# PAGE3.net
KiCad netlist of a schematic drawn in Altium Designer
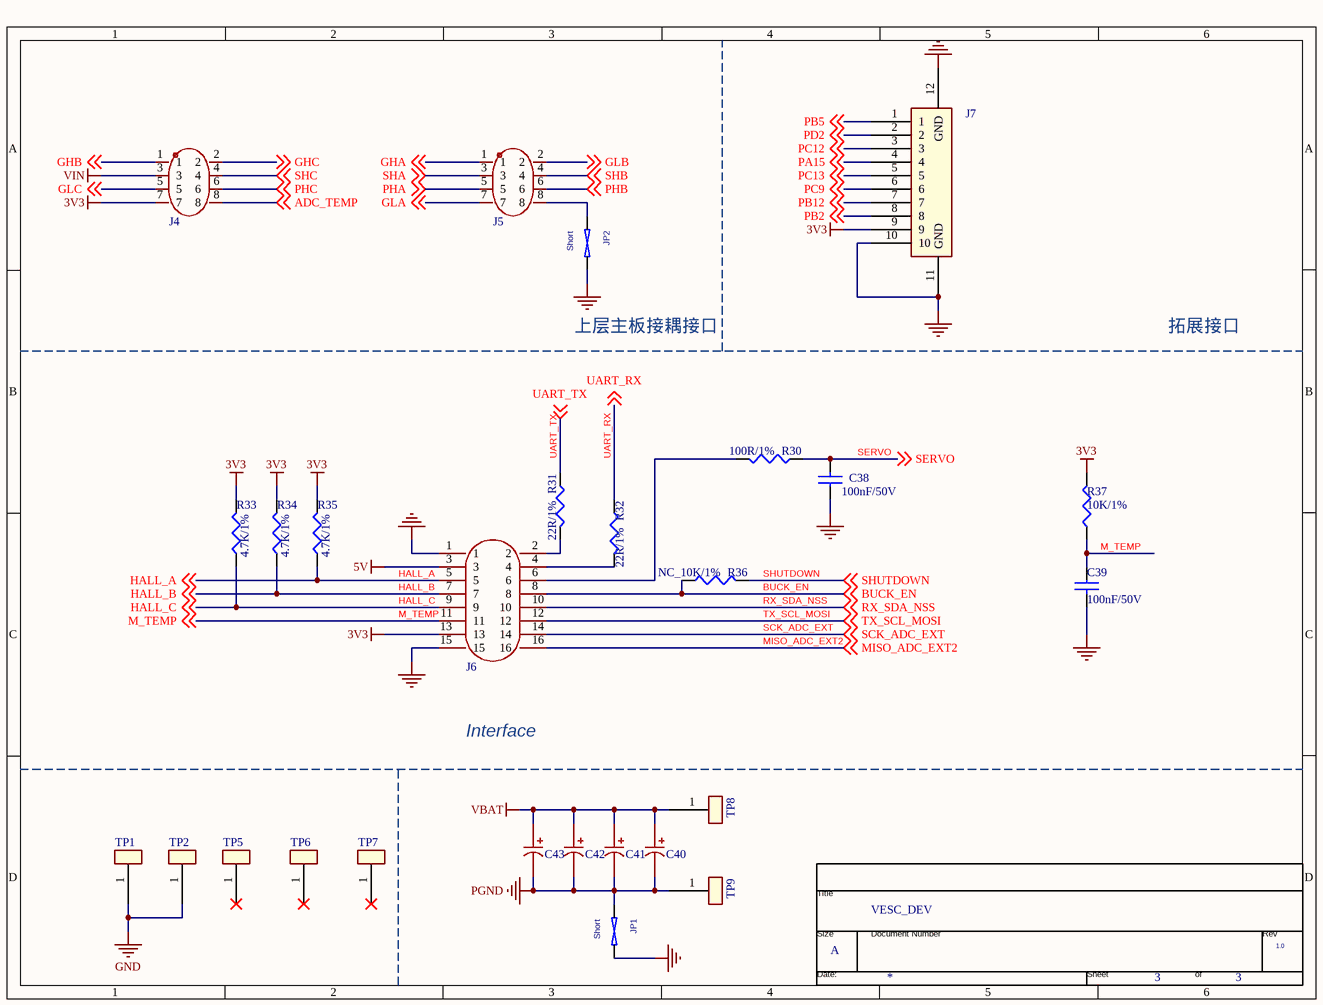
[diagram p0: PAGE3.SchDoc]

(export (version "E")
  (design (tool "Eeschema 10.0.6"))
  (components
    (comp (ref "C38") (value "100nF/50V") (footprint "C0402") (libsource (lib "*") (part "CAP NP")))
    (comp (ref "C39") (value "100nF/50V") (footprint "C0402") (libsource (lib "*") (part "CAP NP")))
    (comp (ref "C40")
      (value "680uF")
      (footprint "CAP-TH_BD10.0-P5.00-D0.6-FD")
      (description "容值:680uF;精度:±20%;额定电压:35V;纹波电流:-;等效串联电阻:-;")
      (fields (field (name "MANUFACTURER") "AISHI(艾华集团)") (field (name "MANUFACTURER PART") "ERS1VM681G16OT"))
      (libsource (lib "VESC_DEVICE_Library") (part "ERS1VM681G16OT"))
    )
    (comp (ref "C41")
      (value "680uF")
      (footprint "CAP-TH_BD10.0-P5.00-D0.6-FD")
      (description "容值:680uF;精度:±20%;额定电压:35V;纹波电流:-;等效串联电阻:-;")
      (fields (field (name "MANUFACTURER") "AISHI(艾华集团)") (field (name "MANUFACTURER PART") "ERS1VM681G16OT"))
      (libsource (lib "VESC_DEVICE_Library") (part "ERS1VM681G16OT"))
    )
    (comp (ref "C42")
      (value "680uF")
      (footprint "CAP-TH_BD10.0-P5.00-D0.6-FD")
      (description "容值:680uF;精度:±20%;额定电压:35V;纹波电流:-;等效串联电阻:-;")
      (fields (field (name "MANUFACTURER") "AISHI(艾华集团)") (field (name "MANUFACTURER PART") "ERS1VM681G16OT"))
      (libsource (lib "VESC_DEVICE_Library") (part "ERS1VM681G16OT"))
    )
    (comp (ref "C43")
      (value "680uF")
      (footprint "CAP-TH_BD10.0-P5.00-D0.6-FD")
      (description "容值:680uF;精度:±20%;额定电压:35V;纹波电流:-;等效串联电阻:-;")
      (fields (field (name "MANUFACTURER") "AISHI(艾华集团)") (field (name "MANUFACTURER PART") "ERS1VM681G16OT"))
      (libsource (lib "VESC_DEVICE_Library") (part "ERS1VM681G16OT"))
    )
    (comp (ref "J4")
      (value "X6521WVS-2x04H-C60D74")
      (footprint "HDR-SMD_8P-P1.27-V-M-C2-C4-LS5.3")
      (fields (field (name "MANUFACTURER") "XKB Connection(中国星坤)"))
      (libsource (lib "VESC_DEVICE_Library") (part "X6521WVS-2x04H-C60D74"))
    )
    (comp (ref "J5")
      (value "X6521WVS-2x04H-C60D74")
      (footprint "HDR-SMD_8P-P1.27-V-M-C2-C4-LS5.3")
      (fields (field (name "MANUFACTURER") "XKB Connection(中国星坤)"))
      (libsource (lib "VESC_DEVICE_Library") (part "X6521WVS-2x04H-C60D74"))
    )
    (comp (ref "J6")
      (value "HC-5557-2*8A")
      (footprint "CONN-TH_HC5557-2X8A")
      (fields (field (name "MANUFACTURER") "HCTL(华灿天禄)"))
      (libsource (lib "VESC_DEVICE_Library") (part "HC-5557-2*8A"))
    )
    (comp (ref "J7")
      (value "1.25-10GH_1")
      (footprint "CONN-SMD_10P-P1.25_JS_GH125-S10CCA-00")
      (libsource (lib "VESC_DEVICE_Library") (part "1.25-10GH_1"))
    )
    (comp (ref "JP1")
      (value "Short")
      (footprint "SHORT")
      (description "2 PIN SHORTED TO CONNECT DIFFERENT NETS")
      (fields (field (name "PART_NUMBER") "TMP-442"))
      (libsource (lib "VESC_DEVICE_Library") (part "SHORT"))
    )
    (comp (ref "JP2")
      (value "Short")
      (footprint "SHORT")
      (description "2 PIN SHORTED TO CONNECT DIFFERENT NETS")
      (fields (field (name "PART_NUMBER") "TMP-442"))
      (libsource (lib "VESC_DEVICE_Library") (part "SHORT"))
    )
    (comp (ref "R30") (value "100R/1%") (footprint "R0402") (libsource (lib "*") (part "RESISTOR")))
    (comp (ref "R31") (value "22R/1%") (footprint "R0402") (libsource (lib "*") (part "RESISTOR")))
    (comp (ref "R32") (value "22R/1%") (footprint "R0402") (libsource (lib "*") (part "RESISTOR")))
    (comp (ref "R33") (value "4.7K/1%") (footprint "R0402") (libsource (lib "*") (part "RESISTOR")))
    (comp (ref "R34") (value "4.7K/1%") (footprint "R0402") (libsource (lib "*") (part "RESISTOR")))
    (comp (ref "R35") (value "4.7K/1%") (footprint "R0402") (libsource (lib "*") (part "RESISTOR")))
    (comp (ref "R36") (value "NC_10K/1%") (footprint "R0402") (libsource (lib "*") (part "RESISTOR")))
    (comp (ref "R37") (value "10K/1%") (footprint "R0402") (libsource (lib "*") (part "RESISTOR")))
    (comp (ref "TP1")
      (value "TEST POINT")
      (footprint "HOLE-4MM_M")
      (libsource (lib "") (part "TEST POINT_1"))
    )
    (comp (ref "TP2")
      (value "TEST POINT")
      (footprint "HOLE-4MM_M")
      (libsource (lib "") (part "TEST POINT_1"))
    )
    (comp (ref "TP5")
      (value "TEST POINT")
      (footprint "HOLE-8MM_M")
      (libsource (lib "") (part "TEST POINT_1"))
    )
    (comp (ref "TP6")
      (value "TEST POINT")
      (footprint "HOLE-8MM_M")
      (libsource (lib "") (part "TEST POINT_1"))
    )
    (comp (ref "TP7")
      (value "TEST POINT")
      (footprint "HOLE-8MM_M")
      (libsource (lib "") (part "TEST POINT_1"))
    )
    (comp (ref "TP8")
      (value "TEST POINT")
      (footprint "HOLE-8MM_M")
      (libsource (lib "VESC_DEVICE_Library") (part "TEST POINT"))
    )
    (comp (ref "TP9")
      (value "TEST POINT")
      (footprint "HOLE-8MM_M")
      (libsource (lib "VESC_DEVICE_Library") (part "TEST POINT"))
    )
  )
  (nets
    (net (code "1") (name "3V3") (class "Default")
      (node (ref "J4") (pin "7") (pinfunction "7_7") (pintype "passive"))
      (node (ref "J6") (pin "13") (pinfunction "13_13") (pintype "passive"))
      (node (ref "J7") (pin "9") (pinfunction "9_9") (pintype "passive"))
      (node (ref "R33") (pin "2") (pinfunction "2_2") (pintype "passive"))
      (node (ref "R34") (pin "2") (pinfunction "2_2") (pintype "passive"))
      (node (ref "R35") (pin "2") (pinfunction "2_2") (pintype "passive"))
      (node (ref "R37") (pin "2") (pinfunction "2_2") (pintype "passive"))
    )
    (net (code "2") (name "5V") (class "Default")
      (node (ref "J6") (pin "3") (pinfunction "3_3") (pintype "passive"))
    )
    (net (code "3") (name "ADC_TEMP") (class "Default")
      (node (ref "J4") (pin "8") (pinfunction "8_8") (pintype "passive"))
    )
    (net (code "4") (name "BUCK_EN") (class "Default")
      (node (ref "J6") (pin "8") (pinfunction "8_8") (pintype "passive"))
      (node (ref "R36") (pin "2") (pinfunction "2_2") (pintype "passive"))
    )
    (net (code "5") (name "GHA") (class "Default")
      (node (ref "J5") (pin "1") (pinfunction "1_1") (pintype "passive"))
    )
    (net (code "6") (name "GHB") (class "Default")
      (node (ref "J4") (pin "1") (pinfunction "1_1") (pintype "passive"))
    )
    (net (code "7") (name "GHC") (class "Default")
      (node (ref "J4") (pin "2") (pinfunction "2_2") (pintype "passive"))
    )
    (net (code "8") (name "GLA") (class "Default")
      (node (ref "J5") (pin "7") (pinfunction "7_7") (pintype "passive"))
    )
    (net (code "9") (name "GLB") (class "Default")
      (node (ref "J5") (pin "2") (pinfunction "2_2") (pintype "passive"))
    )
    (net (code "10") (name "GLC") (class "Default")
      (node (ref "J4") (pin "5") (pinfunction "5_5") (pintype "passive"))
    )
    (net (code "11") (name "GND") (class "Default")
      (node (ref "C38") (pin "1") (pinfunction "1_1") (pintype "passive"))
      (node (ref "C39") (pin "2") (pinfunction "2_2") (pintype "passive"))
      (node (ref "J6") (pin "1") (pinfunction "1_1") (pintype "passive"))
      (node (ref "J6") (pin "15") (pinfunction "15_15") (pintype "passive"))
      (node (ref "J7") (pin "10") (pinfunction "10_10") (pintype "passive"))
      (node (ref "J7") (pin "11") (pinfunction "GND_11") (pintype "passive"))
      (node (ref "J7") (pin "12") (pinfunction "GND_12") (pintype "passive"))
      (node (ref "JP1") (pin "2") (pinfunction "2_2") (pintype "passive"))
      (node (ref "JP2") (pin "2") (pinfunction "2_2") (pintype "passive"))
      (node (ref "TP1") (pin "1") (pinfunction "1_1") (pintype "passive"))
      (node (ref "TP2") (pin "1") (pinfunction "1_1") (pintype "passive"))
    )
    (net (code "12") (name "HALL_A") (class "Default")
      (node (ref "J6") (pin "5") (pinfunction "5_5") (pintype "passive"))
      (node (ref "R35") (pin "1") (pinfunction "1_1") (pintype "passive"))
    )
    (net (code "13") (name "HALL_B") (class "Default")
      (node (ref "J6") (pin "7") (pinfunction "7_7") (pintype "passive"))
      (node (ref "R34") (pin "1") (pinfunction "1_1") (pintype "passive"))
    )
    (net (code "14") (name "HALL_C") (class "Default")
      (node (ref "J6") (pin "9") (pinfunction "9_9") (pintype "passive"))
      (node (ref "R33") (pin "1") (pinfunction "1_1") (pintype "passive"))
    )
    (net (code "15") (name "MISO_ADC_EXT2") (class "Default")
      (node (ref "J6") (pin "16") (pinfunction "16_16") (pintype "passive"))
    )
    (net (code "16") (name "M_TEMP") (class "Default")
      (node (ref "C39") (pin "1") (pinfunction "1_1") (pintype "passive"))
      (node (ref "J6") (pin "11") (pinfunction "11_11") (pintype "passive"))
      (node (ref "R37") (pin "1") (pinfunction "1_1") (pintype "passive"))
    )
    (net (code "17") (name "Net-(J5-Pad8)") (class "Default")
      (node (ref "J5") (pin "8") (pinfunction "8_8") (pintype "passive"))
      (node (ref "JP2") (pin "1") (pinfunction "1_1") (pintype "passive"))
    )
    (net (code "18") (name "Net-(J6-Pad2)") (class "Default")
      (node (ref "J6") (pin "2") (pinfunction "2_2") (pintype "passive"))
      (node (ref "R31") (pin "1") (pinfunction "1_1") (pintype "passive"))
    )
    (net (code "19") (name "Net-(J6-Pad4)") (class "Default")
      (node (ref "J6") (pin "4") (pinfunction "4_4") (pintype "passive"))
      (node (ref "R32") (pin "1") (pinfunction "1_1") (pintype "passive"))
    )
    (net (code "20") (name "Net-(J6-Pad6)") (class "Default")
      (node (ref "J6") (pin "6") (pinfunction "6_6") (pintype "passive"))
      (node (ref "R30") (pin "1") (pinfunction "1_1") (pintype "passive"))
    )
    (net (code "21") (name "PA15") (class "Default")
      (node (ref "J7") (pin "4") (pinfunction "4_4") (pintype "passive"))
    )
    (net (code "22") (name "PB2") (class "Default")
      (node (ref "J7") (pin "8") (pinfunction "8_8") (pintype "passive"))
    )
    (net (code "23") (name "PB5") (class "Default")
      (node (ref "J7") (pin "1") (pinfunction "1_1") (pintype "passive"))
    )
    (net (code "24") (name "PB12") (class "Default")
      (node (ref "J7") (pin "7") (pinfunction "7_7") (pintype "passive"))
    )
    (net (code "25") (name "PC9") (class "Default")
      (node (ref "J7") (pin "6") (pinfunction "6_6") (pintype "passive"))
    )
    (net (code "26") (name "PC12") (class "Default")
      (node (ref "J7") (pin "3") (pinfunction "3_3") (pintype "passive"))
    )
    (net (code "27") (name "PC13") (class "Default")
      (node (ref "J7") (pin "5") (pinfunction "5_5") (pintype "passive"))
    )
    (net (code "28") (name "PD2") (class "Default")
      (node (ref "J7") (pin "2") (pinfunction "2_2") (pintype "passive"))
    )
    (net (code "29") (name "PGND") (class "Default")
      (node (ref "C40") (pin "2") (pinfunction "2_2") (pintype "passive"))
      (node (ref "C41") (pin "2") (pinfunction "2_2") (pintype "passive"))
      (node (ref "C42") (pin "2") (pinfunction "2_2") (pintype "passive"))
      (node (ref "C43") (pin "2") (pinfunction "2_2") (pintype "passive"))
      (node (ref "JP1") (pin "1") (pinfunction "1_1") (pintype "passive"))
      (node (ref "TP9") (pin "1") (pinfunction "1_1") (pintype "passive"))
    )
    (net (code "30") (name "PHA") (class "Default")
      (node (ref "J5") (pin "5") (pinfunction "5_5") (pintype "passive"))
    )
    (net (code "31") (name "PHB") (class "Default")
      (node (ref "J5") (pin "6") (pinfunction "6_6") (pintype "passive"))
    )
    (net (code "32") (name "PHC") (class "Default")
      (node (ref "J4") (pin "6") (pinfunction "6_6") (pintype "passive"))
    )
    (net (code "33") (name "RX_SDA_NSS") (class "Default")
      (node (ref "J6") (pin "10") (pinfunction "10_10") (pintype "passive"))
    )
    (net (code "34") (name "SCK_ADC_EXT") (class "Default")
      (node (ref "J6") (pin "14") (pinfunction "14_14") (pintype "passive"))
    )
    (net (code "35") (name "SERVO") (class "Default")
      (node (ref "C38") (pin "2") (pinfunction "2_2") (pintype "passive"))
      (node (ref "R30") (pin "2") (pinfunction "2_2") (pintype "passive"))
    )
    (net (code "36") (name "SHA") (class "Default")
      (node (ref "J5") (pin "3") (pinfunction "3_3") (pintype "passive"))
    )
    (net (code "37") (name "SHB") (class "Default")
      (node (ref "J5") (pin "4") (pinfunction "4_4") (pintype "passive"))
    )
    (net (code "38") (name "SHC") (class "Default")
      (node (ref "J4") (pin "4") (pinfunction "4_4") (pintype "passive"))
    )
    (net (code "39") (name "SHUTDOWN") (class "Default")
      (node (ref "R36") (pin "1") (pinfunction "1_1") (pintype "passive"))
    )
    (net (code "40") (name "TX_SCL_MOSI") (class "Default")
      (node (ref "J6") (pin "12") (pinfunction "12_12") (pintype "passive"))
    )
    (net (code "41") (name "UART_RX") (class "Default")
      (node (ref "R32") (pin "2") (pinfunction "2_2") (pintype "passive"))
    )
    (net (code "42") (name "UART_TX") (class "Default")
      (node (ref "R31") (pin "2") (pinfunction "2_2") (pintype "passive"))
    )
    (net (code "43") (name "VBAT") (class "Default")
      (node (ref "C40") (pin "1") (pinfunction "1_1") (pintype "passive"))
      (node (ref "C41") (pin "1") (pinfunction "1_1") (pintype "passive"))
      (node (ref "C42") (pin "1") (pinfunction "1_1") (pintype "passive"))
      (node (ref "C43") (pin "1") (pinfunction "1_1") (pintype "passive"))
      (node (ref "TP8") (pin "1") (pinfunction "1_1") (pintype "passive"))
    )
    (net (code "44") (name "VIN") (class "Default")
      (node (ref "J4") (pin "3") (pinfunction "3_3") (pintype "passive"))
    )
    (net (code "45") (name "unconnected-(TP5-Pad1)") (class "Default")
      (node (ref "TP5") (pin "1") (pinfunction "1_1") (pintype "passive+no_connect"))
    )
    (net (code "46") (name "unconnected-(TP6-Pad1)") (class "Default")
      (node (ref "TP6") (pin "1") (pinfunction "1_1") (pintype "passive+no_connect"))
    )
    (net (code "47") (name "unconnected-(TP7-Pad1)") (class "Default")
      (node (ref "TP7") (pin "1") (pinfunction "1_1") (pintype "passive+no_connect"))
    )
  )
)
